# D1MSHO.net
KiCad netlist of a schematic drawn in EAGLE
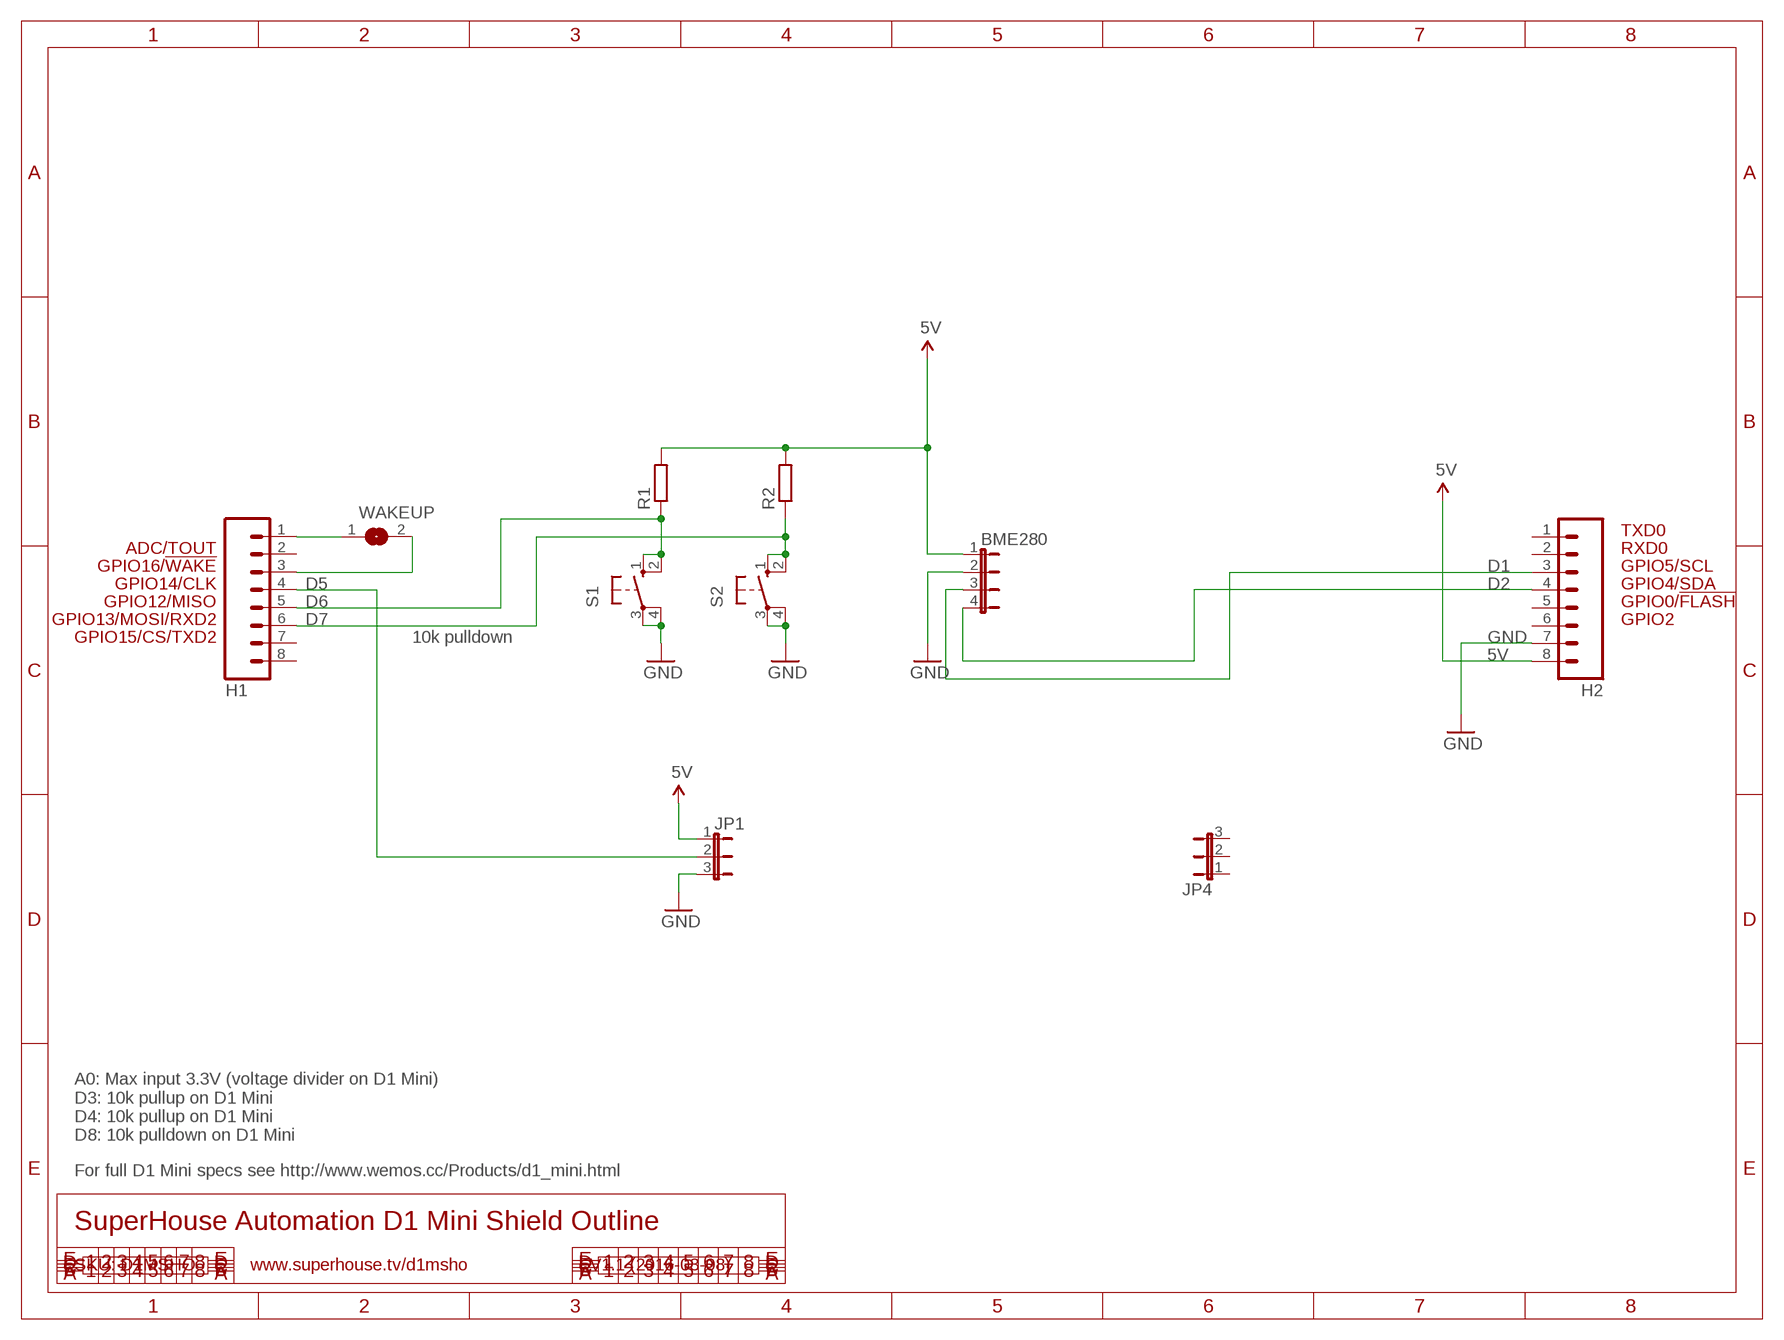
[diagram p0: schematic, sheet 1]

(export (version "E")
  (design (tool "Eeschema 10.0.6"))
  (components
    (comp (ref "BME280")
      (value "JP4E")
      (footprint "eagle-import:JP4")
      (libsource (lib "eagle-import") (part "JP4E"))
    )
    (comp (ref "H1")
      (value "M08")
      (footprint "eagle-import:1X08")
      (libsource (lib "eagle-import") (part "M08"))
    )
    (comp (ref "H2")
      (value "M08")
      (footprint "eagle-import:1X08")
      (libsource (lib "eagle-import") (part "M08"))
    )
    (comp (ref "JP1")
      (value "JP2E")
      (footprint "eagle-import:JP2")
      (libsource (lib "eagle-import") (part "JP2E"))
    )
    (comp (ref "JP4")
      (value "JP2E")
      (footprint "eagle-import:JP2")
      (libsource (lib "eagle-import") (part "JP2E"))
    )
    (comp (ref "R1")
      (value "R-EU_R0805")
      (footprint "eagle-import:R0805")
      (libsource (lib "eagle-import") (part "R-EU_R0805"))
    )
    (comp (ref "R2")
      (value "R-EU_R0805")
      (footprint "eagle-import:R0805")
      (libsource (lib "eagle-import") (part "R-EU_R0805"))
    )
    (comp (ref "S1")
      (value "10-XX")
      (footprint "eagle-import:B3F-10XX")
      (fields (field (name "MPN") "B3F-1000"))
      (libsource (lib "eagle-import") (part "10-XX"))
    )
    (comp (ref "S2")
      (value "10-XX")
      (footprint "eagle-import:B3F-10XX")
      (fields (field (name "MPN") "B3F-1000"))
      (libsource (lib "eagle-import") (part "10-XX"))
    )
    (comp (ref "WAKEUP")
      (value "SJ")
      (footprint "eagle-import:SJ")
      (libsource (lib "eagle-import") (part "SJ"))
    )
  )
  (nets
    (net (code "1") (name "/D1") (class "Default")
      (node (ref "BME280") (pin "3") (pinfunction "3_3") (pintype "passive"))
      (node (ref "H2") (pin "3") (pinfunction "3_3") (pintype "passive"))
    )
    (net (code "2") (name "/D2") (class "Default")
      (node (ref "BME280") (pin "4") (pinfunction "4_4") (pintype "passive"))
      (node (ref "H2") (pin "4") (pinfunction "4_4") (pintype "passive"))
    )
    (net (code "3") (name "/D5") (class "Default")
      (node (ref "H1") (pin "4") (pinfunction "4_4") (pintype "passive"))
      (node (ref "JP1") (pin "2") (pinfunction "2_2") (pintype "passive"))
    )
    (net (code "4") (name "/D6") (class "Default")
      (node (ref "H1") (pin "5") (pinfunction "5_5") (pintype "passive"))
      (node (ref "R1") (pin "1") (pinfunction "1_1") (pintype "passive"))
      (node (ref "S1") (pin "1") (pinfunction "S_1") (pintype "passive"))
      (node (ref "S1") (pin "2") (pinfunction "S1_2") (pintype "passive"))
    )
    (net (code "5") (name "/D7") (class "Default")
      (node (ref "H1") (pin "6") (pinfunction "6_6") (pintype "passive"))
      (node (ref "R2") (pin "1") (pinfunction "1_1") (pintype "passive"))
      (node (ref "S2") (pin "1") (pinfunction "S_1") (pintype "passive"))
      (node (ref "S2") (pin "2") (pinfunction "S1_2") (pintype "passive"))
    )
    (net (code "6") (name "5V") (class "Default")
      (node (ref "BME280") (pin "1") (pinfunction "1_1") (pintype "passive"))
      (node (ref "H2") (pin "8") (pinfunction "8_8") (pintype "passive"))
      (node (ref "JP1") (pin "1") (pinfunction "1_1") (pintype "passive"))
      (node (ref "R1") (pin "2") (pinfunction "2_2") (pintype "passive"))
      (node (ref "R2") (pin "2") (pinfunction "2_2") (pintype "passive"))
    )
    (net (code "7") (name "GND") (class "Default")
      (node (ref "BME280") (pin "2") (pinfunction "2_2") (pintype "passive"))
      (node (ref "H2") (pin "7") (pinfunction "7_7") (pintype "passive"))
      (node (ref "JP1") (pin "3") (pinfunction "3_3") (pintype "passive"))
      (node (ref "S1") (pin "3") (pinfunction "P_3") (pintype "passive"))
      (node (ref "S1") (pin "4") (pinfunction "P1_4") (pintype "passive"))
      (node (ref "S2") (pin "3") (pinfunction "P_3") (pintype "passive"))
      (node (ref "S2") (pin "4") (pinfunction "P1_4") (pintype "passive"))
    )
    (net (code "8") (name "Net-(H1-Pad1)") (class "Default")
      (node (ref "H1") (pin "1") (pinfunction "1_1") (pintype "passive"))
      (node (ref "WAKEUP") (pin "1") (pinfunction "1_1") (pintype "passive"))
    )
    (net (code "9") (name "Net-(H1-Pad3)") (class "Default")
      (node (ref "H1") (pin "3") (pinfunction "3_3") (pintype "passive"))
      (node (ref "WAKEUP") (pin "2") (pinfunction "2_2") (pintype "passive"))
    )
    (net (code "10") (name "unconnected-(H1-Pad2)") (class "Default")
      (node (ref "H1") (pin "2") (pinfunction "2_2") (pintype "passive"))
    )
    (net (code "11") (name "unconnected-(H1-Pad7)") (class "Default")
      (node (ref "H1") (pin "7") (pinfunction "7_7") (pintype "passive"))
    )
    (net (code "12") (name "unconnected-(H1-Pad8)") (class "Default")
      (node (ref "H1") (pin "8") (pinfunction "8_8") (pintype "passive"))
    )
    (net (code "13") (name "unconnected-(H2-Pad1)") (class "Default")
      (node (ref "H2") (pin "1") (pinfunction "1_1") (pintype "passive"))
    )
    (net (code "14") (name "unconnected-(H2-Pad2)") (class "Default")
      (node (ref "H2") (pin "2") (pinfunction "2_2") (pintype "passive"))
    )
    (net (code "15") (name "unconnected-(H2-Pad5)") (class "Default")
      (node (ref "H2") (pin "5") (pinfunction "5_5") (pintype "passive"))
    )
    (net (code "16") (name "unconnected-(H2-Pad6)") (class "Default")
      (node (ref "H2") (pin "6") (pinfunction "6_6") (pintype "passive"))
    )
    (net (code "17") (name "unconnected-(JP4-Pad1)") (class "Default")
      (node (ref "JP4") (pin "1") (pinfunction "1_1") (pintype "passive"))
    )
    (net (code "18") (name "unconnected-(JP4-Pad2)") (class "Default")
      (node (ref "JP4") (pin "2") (pinfunction "2_2") (pintype "passive"))
    )
    (net (code "19") (name "unconnected-(JP4-Pad3)") (class "Default")
      (node (ref "JP4") (pin "3") (pinfunction "3_3") (pintype "passive"))
    )
  )
)
